# ALU_Ctrl.net
KiCad netlist of a schematic drawn in Altium Designer
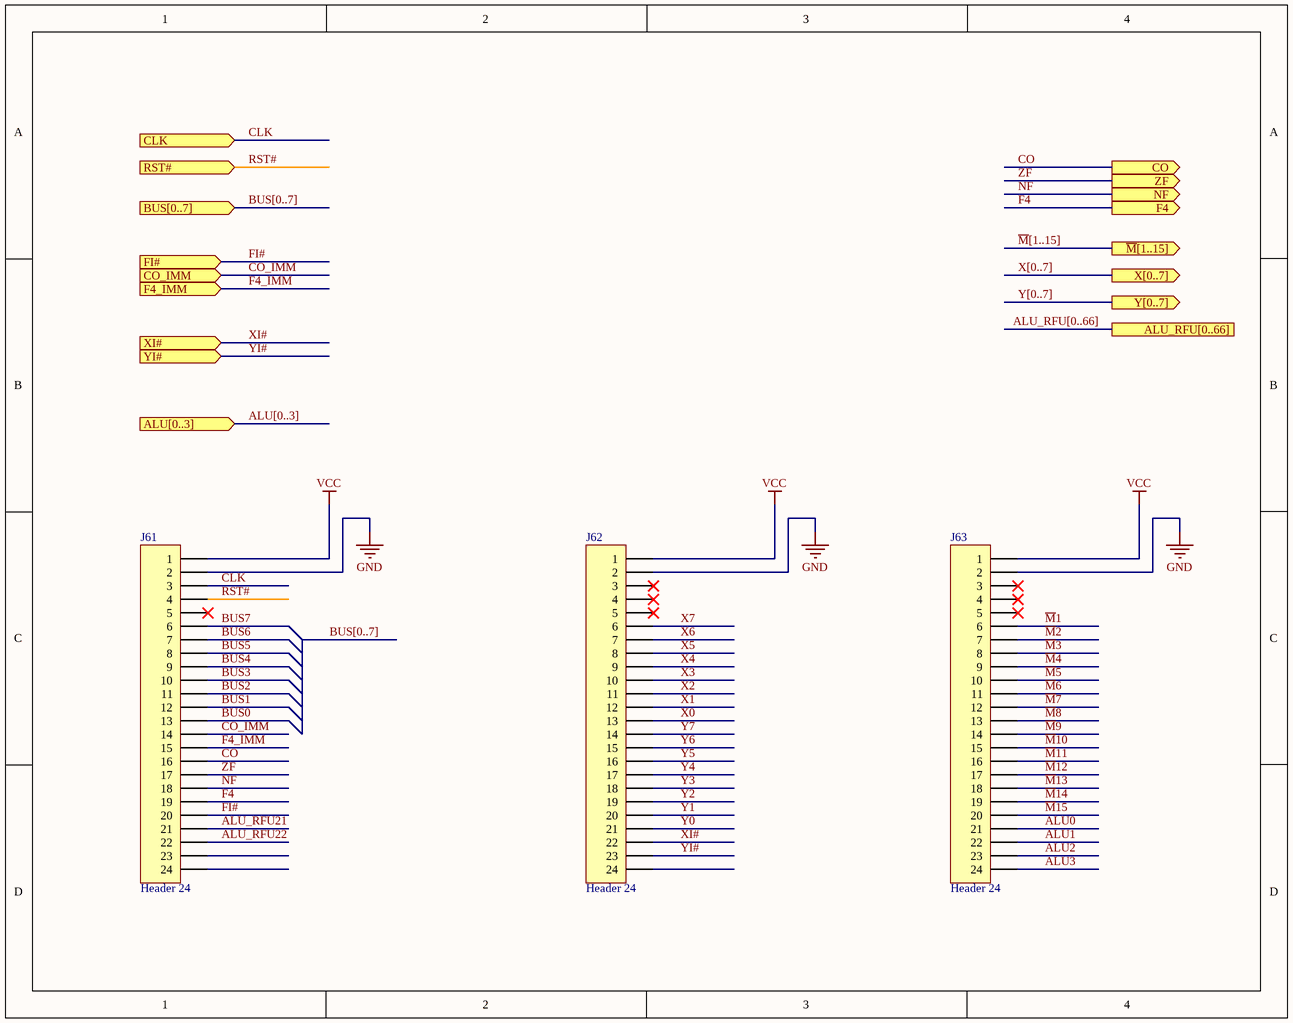
[diagram p0: ALU_Ctrl.SchDoc]

(export (version "E")
  (design (tool "Eeschema 10.0.6"))
  (components
    (comp (ref "J61")
      (value "Header 24")
      (footprint "HDR1X24")
      (description "Header, 24-Pin")
      (fields (field (name "PUBLISHER") "Altium Limited"))
      (libsource (lib "Miscellaneous Connectors") (part "Header 24"))
    )
    (comp (ref "J62")
      (value "Header 24")
      (footprint "HDR1X24")
      (description "Header, 24-Pin")
      (fields (field (name "PUBLISHER") "Altium Limited"))
      (libsource (lib "Miscellaneous Connectors") (part "Header 24"))
    )
    (comp (ref "J63")
      (value "Header 24")
      (footprint "HDR1X24")
      (description "Header, 24-Pin")
      (fields (field (name "PUBLISHER") "Altium Limited"))
      (libsource (lib "Miscellaneous Connectors") (part "Header 24"))
    )
  )
  (nets
    (net (code "66") (name "/ALU0") (class "Default")
      (node (ref "J63") (pin "21") (pinfunction "21_21") (pintype "passive"))
    )
    (net (code "67") (name "/ALU1") (class "Default")
      (node (ref "J63") (pin "22") (pinfunction "22_22") (pintype "passive"))
    )
    (net (code "68") (name "/ALU2") (class "Default")
      (node (ref "J63") (pin "23") (pinfunction "23_23") (pintype "passive"))
    )
    (net (code "69") (name "/ALU3") (class "Default")
      (node (ref "J63") (pin "24") (pinfunction "24_24") (pintype "passive"))
    )
    (net (code "71") (name "/ALU_RFU21") (class "Default")
      (node (ref "J61") (pin "21") (pinfunction "21_21") (pintype "passive"))
    )
    (net (code "72") (name "/ALU_RFU22") (class "Default")
      (node (ref "J61") (pin "22") (pinfunction "22_22") (pintype "passive"))
    )
    (net (code "74") (name "/BUS0") (class "Default")
      (node (ref "J61") (pin "13") (pinfunction "13_13") (pintype "passive"))
    )
    (net (code "75") (name "/BUS1") (class "Default")
      (node (ref "J61") (pin "12") (pinfunction "12_12") (pintype "passive"))
    )
    (net (code "76") (name "/BUS2") (class "Default")
      (node (ref "J61") (pin "11") (pinfunction "11_11") (pintype "passive"))
    )
    (net (code "77") (name "/BUS3") (class "Default")
      (node (ref "J61") (pin "10") (pinfunction "10_10") (pintype "passive"))
    )
    (net (code "78") (name "/BUS4") (class "Default")
      (node (ref "J61") (pin "9") (pinfunction "9_9") (pintype "passive"))
    )
    (net (code "79") (name "/BUS5") (class "Default")
      (node (ref "J61") (pin "8") (pinfunction "8_8") (pintype "passive"))
    )
    (net (code "80") (name "/BUS6") (class "Default")
      (node (ref "J61") (pin "7") (pinfunction "7_7") (pintype "passive"))
    )
    (net (code "81") (name "/BUS7") (class "Default")
      (node (ref "J61") (pin "6") (pinfunction "6_6") (pintype "passive"))
    )
    (net (code "83") (name "/CLK") (class "Default")
      (node (ref "J61") (pin "3") (pinfunction "3_3") (pintype "passive"))
    )
    (net (code "84") (name "/CO") (class "Default")
      (node (ref "J61") (pin "16") (pinfunction "16_16") (pintype "passive"))
    )
    (net (code "85") (name "/CO_IMM") (class "Default")
      (node (ref "J61") (pin "14") (pinfunction "14_14") (pintype "passive"))
    )
    (net (code "86") (name "/F4") (class "Default")
      (node (ref "J61") (pin "19") (pinfunction "19_19") (pintype "passive"))
    )
    (net (code "87") (name "/F4_IMM") (class "Default")
      (node (ref "J61") (pin "15") (pinfunction "15_15") (pintype "passive"))
    )
    (net (code "88") (name "/FI#") (class "Default")
      (node (ref "J61") (pin "20") (pinfunction "20_20") (pintype "passive"))
    )
    (net (code "89") (name "/NF") (class "Default")
      (node (ref "J61") (pin "18") (pinfunction "18_18") (pintype "passive"))
    )
    (net (code "90") (name "/RST#") (class "Default")
      (node (ref "J61") (pin "4") (pinfunction "4_4") (pintype "passive"))
    )
    (net (code "91") (name "/X0") (class "Default")
      (node (ref "J62") (pin "13") (pinfunction "13_13") (pintype "passive"))
    )
    (net (code "92") (name "/X1") (class "Default")
      (node (ref "J62") (pin "12") (pinfunction "12_12") (pintype "passive"))
    )
    (net (code "93") (name "/X2") (class "Default")
      (node (ref "J62") (pin "11") (pinfunction "11_11") (pintype "passive"))
    )
    (net (code "94") (name "/X3") (class "Default")
      (node (ref "J62") (pin "10") (pinfunction "10_10") (pintype "passive"))
    )
    (net (code "95") (name "/X4") (class "Default")
      (node (ref "J62") (pin "9") (pinfunction "9_9") (pintype "passive"))
    )
    (net (code "96") (name "/X5") (class "Default")
      (node (ref "J62") (pin "8") (pinfunction "8_8") (pintype "passive"))
    )
    (net (code "97") (name "/X6") (class "Default")
      (node (ref "J62") (pin "7") (pinfunction "7_7") (pintype "passive"))
    )
    (net (code "98") (name "/X7") (class "Default")
      (node (ref "J62") (pin "6") (pinfunction "6_6") (pintype "passive"))
    )
    (net (code "99") (name "/XI#") (class "Default")
      (node (ref "J62") (pin "22") (pinfunction "22_22") (pintype "passive"))
    )
    (net (code "101") (name "/Y0") (class "Default")
      (node (ref "J62") (pin "21") (pinfunction "21_21") (pintype "passive"))
    )
    (net (code "102") (name "/Y1") (class "Default")
      (node (ref "J62") (pin "20") (pinfunction "20_20") (pintype "passive"))
    )
    (net (code "103") (name "/Y2") (class "Default")
      (node (ref "J62") (pin "19") (pinfunction "19_19") (pintype "passive"))
    )
    (net (code "104") (name "/Y3") (class "Default")
      (node (ref "J62") (pin "18") (pinfunction "18_18") (pintype "passive"))
    )
    (net (code "105") (name "/Y4") (class "Default")
      (node (ref "J62") (pin "17") (pinfunction "17_17") (pintype "passive"))
    )
    (net (code "106") (name "/Y5") (class "Default")
      (node (ref "J62") (pin "16") (pinfunction "16_16") (pintype "passive"))
    )
    (net (code "107") (name "/Y6") (class "Default")
      (node (ref "J62") (pin "15") (pinfunction "15_15") (pintype "passive"))
    )
    (net (code "108") (name "/Y7") (class "Default")
      (node (ref "J62") (pin "14") (pinfunction "14_14") (pintype "passive"))
    )
    (net (code "109") (name "/YI#") (class "Default")
      (node (ref "J62") (pin "23") (pinfunction "23_23") (pintype "passive"))
    )
    (net (code "111") (name "/ZF") (class "Default")
      (node (ref "J61") (pin "17") (pinfunction "17_17") (pintype "passive"))
    )
    (net (code "112") (name "/~{M}1") (class "Default")
      (node (ref "J63") (pin "6") (pinfunction "6_6") (pintype "passive"))
    )
    (net (code "113") (name "/~{M}2") (class "Default")
      (node (ref "J63") (pin "7") (pinfunction "7_7") (pintype "passive"))
    )
    (net (code "114") (name "/~{M}3") (class "Default")
      (node (ref "J63") (pin "8") (pinfunction "8_8") (pintype "passive"))
    )
    (net (code "115") (name "/~{M}4") (class "Default")
      (node (ref "J63") (pin "9") (pinfunction "9_9") (pintype "passive"))
    )
    (net (code "116") (name "/~{M}5") (class "Default")
      (node (ref "J63") (pin "10") (pinfunction "10_10") (pintype "passive"))
    )
    (net (code "117") (name "/~{M}6") (class "Default")
      (node (ref "J63") (pin "11") (pinfunction "11_11") (pintype "passive"))
    )
    (net (code "118") (name "/~{M}7") (class "Default")
      (node (ref "J63") (pin "12") (pinfunction "12_12") (pintype "passive"))
    )
    (net (code "119") (name "/~{M}8") (class "Default")
      (node (ref "J63") (pin "13") (pinfunction "13_13") (pintype "passive"))
    )
    (net (code "120") (name "/~{M}9") (class "Default")
      (node (ref "J63") (pin "14") (pinfunction "14_14") (pintype "passive"))
    )
    (net (code "121") (name "/~{M}10") (class "Default")
      (node (ref "J63") (pin "15") (pinfunction "15_15") (pintype "passive"))
    )
    (net (code "122") (name "/~{M}11") (class "Default")
      (node (ref "J63") (pin "16") (pinfunction "16_16") (pintype "passive"))
    )
    (net (code "123") (name "/~{M}12") (class "Default")
      (node (ref "J63") (pin "17") (pinfunction "17_17") (pintype "passive"))
    )
    (net (code "124") (name "/~{M}13") (class "Default")
      (node (ref "J63") (pin "18") (pinfunction "18_18") (pintype "passive"))
    )
    (net (code "125") (name "/~{M}14") (class "Default")
      (node (ref "J63") (pin "19") (pinfunction "19_19") (pintype "passive"))
    )
    (net (code "126") (name "/~{M}15") (class "Default")
      (node (ref "J63") (pin "20") (pinfunction "20_20") (pintype "passive"))
    )
    (net (code "128") (name "GND") (class "Default")
      (node (ref "J61") (pin "2") (pinfunction "2_2") (pintype "passive"))
      (node (ref "J62") (pin "2") (pinfunction "2_2") (pintype "passive"))
      (node (ref "J63") (pin "2") (pinfunction "2_2") (pintype "passive"))
    )
    (net (code "129") (name "VCC") (class "Default")
      (node (ref "J61") (pin "1") (pinfunction "1_1") (pintype "passive"))
      (node (ref "J62") (pin "1") (pinfunction "1_1") (pintype "passive"))
      (node (ref "J63") (pin "1") (pinfunction "1_1") (pintype "passive"))
    )
    (net (code "130") (name "unconnected-(J61-Pad5)") (class "Default")
      (node (ref "J61") (pin "5") (pinfunction "5_5") (pintype "passive+no_connect"))
    )
    (net (code "131") (name "unconnected-(J61-Pad23)") (class "Default")
      (node (ref "J61") (pin "23") (pinfunction "23_23") (pintype "passive"))
    )
    (net (code "132") (name "unconnected-(J61-Pad24)") (class "Default")
      (node (ref "J61") (pin "24") (pinfunction "24_24") (pintype "passive"))
    )
    (net (code "133") (name "unconnected-(J62-Pad3)") (class "Default")
      (node (ref "J62") (pin "3") (pinfunction "3_3") (pintype "passive+no_connect"))
    )
    (net (code "134") (name "unconnected-(J62-Pad4)") (class "Default")
      (node (ref "J62") (pin "4") (pinfunction "4_4") (pintype "passive+no_connect"))
    )
    (net (code "135") (name "unconnected-(J62-Pad5)") (class "Default")
      (node (ref "J62") (pin "5") (pinfunction "5_5") (pintype "passive+no_connect"))
    )
    (net (code "136") (name "unconnected-(J62-Pad24)") (class "Default")
      (node (ref "J62") (pin "24") (pinfunction "24_24") (pintype "passive"))
    )
    (net (code "137") (name "unconnected-(J63-Pad3)") (class "Default")
      (node (ref "J63") (pin "3") (pinfunction "3_3") (pintype "passive+no_connect"))
    )
    (net (code "138") (name "unconnected-(J63-Pad4)") (class "Default")
      (node (ref "J63") (pin "4") (pinfunction "4_4") (pintype "passive+no_connect"))
    )
    (net (code "139") (name "unconnected-(J63-Pad5)") (class "Default")
      (node (ref "J63") (pin "5") (pinfunction "5_5") (pintype "passive+no_connect"))
    )
  )
)
